# AT24-Timer.net
KiCad netlist of a schematic drawn in EAGLE
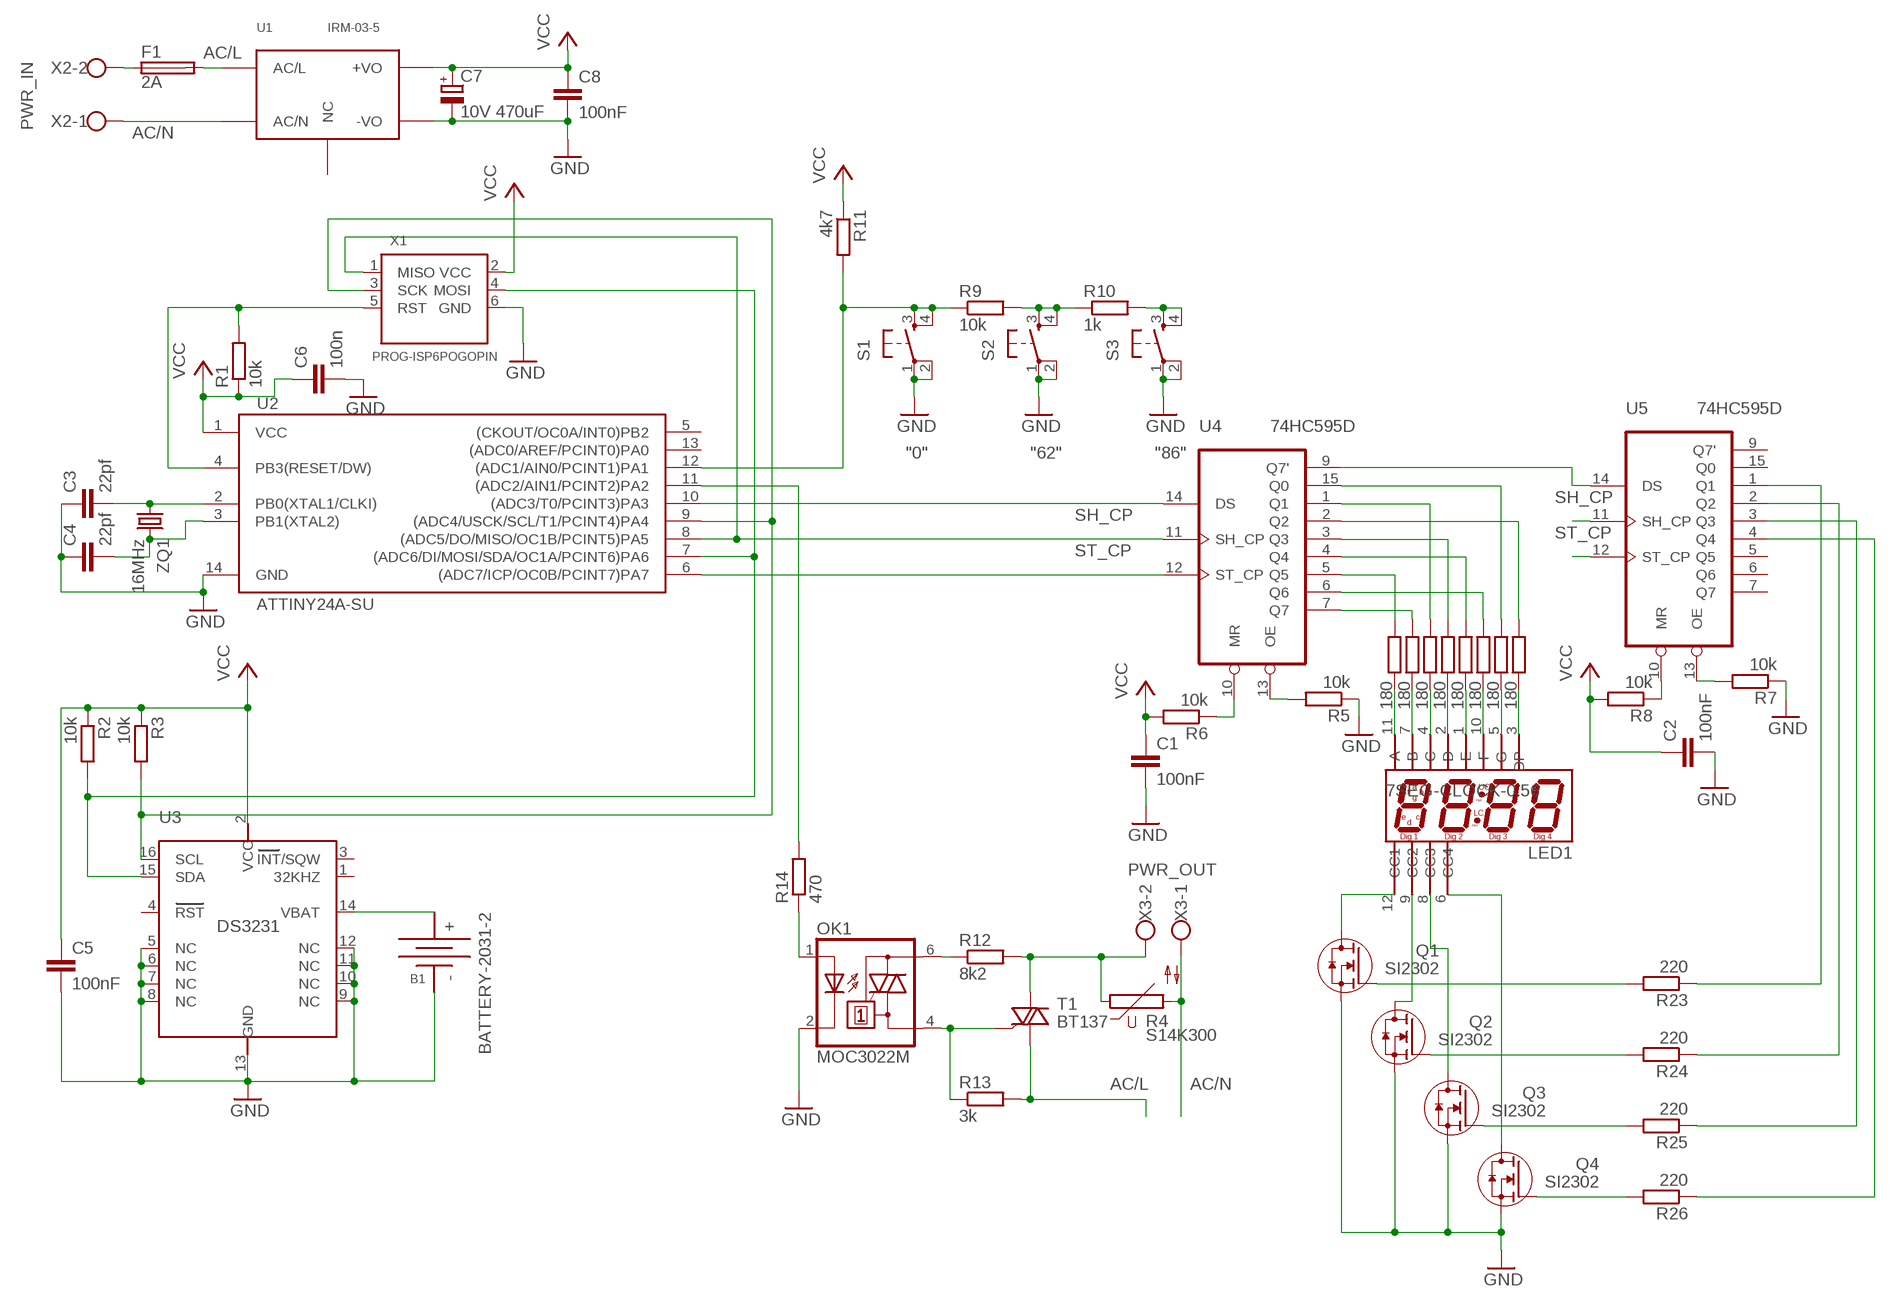
[diagram p0: schematic, sheet 1]

(export (version "E")
  (design (tool "Eeschema 10.0.6"))
  (components
    (comp (ref "B1")
      (value "BATTERY-2031-2")
      (footprint "eagle-import:BTH2032-2")
      (libsource (lib "eagle-import") (part "BATTERY-2031-2"))
    )
    (comp (ref "C1")
      (value "100nF")
      (footprint "eagle-import:C0603")
      (libsource (lib "eagle-import") (part "C-EUC0603"))
    )
    (comp (ref "C2")
      (value "100nF")
      (footprint "eagle-import:C0603")
      (libsource (lib "eagle-import") (part "C-EUC0603"))
    )
    (comp (ref "C3")
      (value "22pf")
      (footprint "eagle-import:C0603")
      (libsource (lib "eagle-import") (part "C-EUC0603"))
    )
    (comp (ref "C4")
      (value "22pf")
      (footprint "eagle-import:C0603")
      (libsource (lib "eagle-import") (part "C-EUC0603"))
    )
    (comp (ref "C5")
      (value "100nF")
      (footprint "eagle-import:C0603")
      (libsource (lib "eagle-import") (part "C-EUC0603"))
    )
    (comp (ref "C6")
      (value "100n")
      (footprint "eagle-import:C0603")
      (libsource (lib "eagle-import") (part "C-EUC0603"))
    )
    (comp (ref "C7")
      (value "10V 470uF")
      (footprint "eagle-import:D_7343-31W")
      (libsource (lib "eagle-import") (part "CPOL-EUD/7343-31W"))
    )
    (comp (ref "C8")
      (value "100nF")
      (footprint "eagle-import:C0805")
      (libsource (lib "eagle-import") (part "C-EUC0805"))
    )
    (comp (ref "F1")
      (value "2A")
      (footprint "eagle-import:SH22,5A")
      (fields (field (name "MPN") "0031.7701.11"))
      (libsource (lib "eagle-import") (part "SH22,5A"))
    )
    (comp (ref "LED1")
      (value "7SEG-CLOCK-0.56")
      (footprint "eagle-import:7SEG_4DIG_0.56")
      (libsource (lib "eagle-import") (part "7SEG-CLOCK-0.56"))
    )
    (comp (ref "OK1")
      (value "MOC3022M")
      (footprint "eagle-import:DIL06")
      (fields (field (name "MF") "FAIRCHILD SEMICONDUCTOR") (field (name "MPN") "MOC3022-M"))
      (libsource (lib "eagle-import") (part "MOC30M22"))
    )
    (comp (ref "Q1")
      (value "SI2302")
      (footprint "eagle-import:SOT-23-GSD")
      (libsource (lib "eagle-import") (part "SI2302"))
    )
    (comp (ref "Q2")
      (value "SI2302")
      (footprint "eagle-import:SOT-23-GSD")
      (libsource (lib "eagle-import") (part "SI2302"))
    )
    (comp (ref "Q3")
      (value "SI2302")
      (footprint "eagle-import:SOT-23-GSD")
      (libsource (lib "eagle-import") (part "SI2302"))
    )
    (comp (ref "Q4")
      (value "SI2302")
      (footprint "eagle-import:SOT-23-GSD")
      (libsource (lib "eagle-import") (part "SI2302"))
    )
    (comp (ref "R1")
      (value "10k")
      (footprint "eagle-import:R0805")
      (libsource (lib "eagle-import") (part "R-EU_R0805"))
    )
    (comp (ref "R2")
      (value "10k")
      (footprint "eagle-import:R0805")
      (libsource (lib "eagle-import") (part "R-EU_R0805"))
    )
    (comp (ref "R3")
      (value "10k")
      (footprint "eagle-import:R0805")
      (libsource (lib "eagle-import") (part "R-EU_R0805"))
    )
    (comp (ref "R4")
      (value "S14K300")
      (footprint "eagle-import:S14K300")
      (libsource (lib "eagle-import") (part "S14K300"))
    )
    (comp (ref "R5")
      (value "10k")
      (footprint "eagle-import:R0805")
      (libsource (lib "eagle-import") (part "R-EU_R0805"))
    )
    (comp (ref "R6")
      (value "10k")
      (footprint "eagle-import:R0805")
      (libsource (lib "eagle-import") (part "R-EU_R0805"))
    )
    (comp (ref "R7")
      (value "10k")
      (footprint "eagle-import:R0805")
      (libsource (lib "eagle-import") (part "R-EU_R0805"))
    )
    (comp (ref "R8")
      (value "10k")
      (footprint "eagle-import:R0805")
      (libsource (lib "eagle-import") (part "R-EU_R0805"))
    )
    (comp (ref "R9")
      (value "10k")
      (footprint "eagle-import:R0805")
      (libsource (lib "eagle-import") (part "R-EU_R0805"))
    )
    (comp (ref "R10")
      (value "1k")
      (footprint "eagle-import:R0805")
      (libsource (lib "eagle-import") (part "R-EU_R0805"))
    )
    (comp (ref "R11")
      (value "4k7")
      (footprint "eagle-import:R0805")
      (libsource (lib "eagle-import") (part "R-EU_R0805"))
    )
    (comp (ref "R12")
      (value "8k2")
      (footprint "eagle-import:0207_7")
      (libsource (lib "eagle-import") (part "R-EU_0207/7"))
    )
    (comp (ref "R13")
      (value "3k")
      (footprint "eagle-import:0207_7")
      (libsource (lib "eagle-import") (part "R-EU_0207/7"))
    )
    (comp (ref "R14")
      (value "470")
      (footprint "eagle-import:R0805")
      (libsource (lib "eagle-import") (part "R-EU_R0805"))
    )
    (comp (ref "R15")
      (value "180")
      (footprint "eagle-import:R0805")
      (libsource (lib "eagle-import") (part "R-EU_R0805"))
    )
    (comp (ref "R16")
      (value "180")
      (footprint "eagle-import:R0805")
      (libsource (lib "eagle-import") (part "R-EU_R0805"))
    )
    (comp (ref "R17")
      (value "180")
      (footprint "eagle-import:R0805")
      (libsource (lib "eagle-import") (part "R-EU_R0805"))
    )
    (comp (ref "R18")
      (value "180")
      (footprint "eagle-import:R0805")
      (libsource (lib "eagle-import") (part "R-EU_R0805"))
    )
    (comp (ref "R19")
      (value "180")
      (footprint "eagle-import:R0805")
      (libsource (lib "eagle-import") (part "R-EU_R0805"))
    )
    (comp (ref "R20")
      (value "180")
      (footprint "eagle-import:R0805")
      (libsource (lib "eagle-import") (part "R-EU_R0805"))
    )
    (comp (ref "R21")
      (value "180")
      (footprint "eagle-import:R0805")
      (libsource (lib "eagle-import") (part "R-EU_R0805"))
    )
    (comp (ref "R22")
      (value "180")
      (footprint "eagle-import:R0805")
      (libsource (lib "eagle-import") (part "R-EU_R0805"))
    )
    (comp (ref "R23")
      (value "220")
      (footprint "eagle-import:R0805")
      (libsource (lib "eagle-import") (part "R-EU_R0805"))
    )
    (comp (ref "R24")
      (value "220")
      (footprint "eagle-import:R0805")
      (libsource (lib "eagle-import") (part "R-EU_R0805"))
    )
    (comp (ref "R25")
      (value "220")
      (footprint "eagle-import:R0805")
      (libsource (lib "eagle-import") (part "R-EU_R0805"))
    )
    (comp (ref "R26")
      (value "220")
      (footprint "eagle-import:R0805")
      (libsource (lib "eagle-import") (part "R-EU_R0805"))
    )
    (comp (ref "S1")
      (value "DTS-6")
      (footprint "eagle-import:DTS-6")
      (libsource (lib "eagle-import") (part "DTS-6"))
    )
    (comp (ref "S2")
      (value "DTS-6")
      (footprint "eagle-import:DTS-6")
      (libsource (lib "eagle-import") (part "DTS-6"))
    )
    (comp (ref "S3")
      (value "DTS-6")
      (footprint "eagle-import:DTS-6")
      (libsource (lib "eagle-import") (part "DTS-6"))
    )
    (comp (ref "T1")
      (value "BT137")
      (footprint "eagle-import:TO220AB")
      (libsource (lib "eagle-import") (part "BT136"))
    )
    (comp (ref "U1")
      (value "IRM-03-5")
      (footprint "eagle-import:IRM-03-_")
      (libsource (lib "eagle-import") (part "IRM-03-5"))
    )
    (comp (ref "U2")
      (value "ATTINY24A-SU")
      (footprint "eagle-import:SO14")
      (libsource (lib "eagle-import") (part "ATTINY24A-SU"))
    )
    (comp (ref "U3")
      (value "DS3231")
      (footprint "eagle-import:SO16L")
      (libsource (lib "eagle-import") (part "DS3231"))
    )
    (comp (ref "U4")
      (value "74HC595D")
      (footprint "eagle-import:SO16")
      (libsource (lib "eagle-import") (part "74595DHC"))
    )
    (comp (ref "U5")
      (value "74HC595D")
      (footprint "eagle-import:SO16")
      (libsource (lib "eagle-import") (part "74595DHC"))
    )
    (comp (ref "X1")
      (value "PROG-ISP6POGOPIN")
      (footprint "eagle-import:PROG_POGOPIN")
      (libsource (lib "eagle-import") (part "PROG-ISP6POGOPIN"))
    )
    (comp (ref "X2")
      (value "PWR_IN")
      (footprint "eagle-import:W237-102")
      (fields (field (name "MPN") "237-102"))
      (libsource (lib "eagle-import") (part "W237-102"))
    )
    (comp (ref "X3")
      (value "PWR_OUT")
      (footprint "eagle-import:W237-102")
      (fields (field (name "MPN") "237-102"))
      (libsource (lib "eagle-import") (part "W237-102"))
    )
    (comp (ref "ZQ1")
      (value "16MHz")
      (footprint "eagle-import:HC49_S")
      (libsource (lib "eagle-import") (part "CRYSTALHC49S"))
    )
  )
  (nets
    (net (code "1") (name "/AC{slash}L") (class "Default")
      (node (ref "F1") (pin "2") (pinfunction "2_2") (pintype "passive"))
      (node (ref "R13") (pin "2") (pinfunction "2_2") (pintype "passive"))
      (node (ref "T1") (pin "1") (pinfunction "A1_1") (pintype "passive"))
      (node (ref "U1") (pin "P$1") (pinfunction "AC/L_P$1") (pintype "power_in"))
    )
    (net (code "2") (name "/AC{slash}N") (class "Default")
      (node (ref "R4") (pin "2") (pinfunction "2_2") (pintype "passive"))
      (node (ref "U1") (pin "P$2") (pinfunction "AC/N_P$2") (pintype "power_in"))
      (node (ref "X2") (pin "1") (pinfunction "KL_1") (pintype "passive"))
      (node (ref "X3") (pin "1") (pinfunction "KL_1") (pintype "passive"))
    )
    (net (code "3") (name "/NC") (class "Default")
      (node (ref "U1") (pin "P$3") (pinfunction "NC_P$3") (pintype "power_in"))
    )
    (net (code "4") (name "/SH_CP") (class "Default")
      (node (ref "U2") (pin "8") (pinfunction "(ADC5/DO/MISO/OC1B/PCINT5)PA5_8") (pintype "bidirectional"))
      (node (ref "U4") (pin "11") (pinfunction "SH_CP_11") (pintype "input"))
      (node (ref "U5") (pin "11") (pinfunction "SH_CP_11") (pintype "input"))
      (node (ref "X1") (pin "1") (pinfunction "MISO_1") (pintype "bidirectional"))
    )
    (net (code "5") (name "/ST_CP") (class "Default")
      (node (ref "U2") (pin "6") (pinfunction "(ADC7/ICP/OC0B/PCINT7)PA7_6") (pintype "bidirectional"))
      (node (ref "U4") (pin "12") (pinfunction "ST_CP_12") (pintype "input"))
      (node (ref "U5") (pin "12") (pinfunction "ST_CP_12") (pintype "input"))
    )
    (net (code "6") (name "GND") (class "Default")
      (node (ref "B1") (pin "-") (pinfunction "-_-") (pintype "power_in"))
      (node (ref "C1") (pin "2") (pinfunction "2_2") (pintype "passive"))
      (node (ref "C2") (pin "2") (pinfunction "2_2") (pintype "passive"))
      (node (ref "C3") (pin "1") (pinfunction "1_1") (pintype "passive"))
      (node (ref "C4") (pin "1") (pinfunction "1_1") (pintype "passive"))
      (node (ref "C5") (pin "2") (pinfunction "2_2") (pintype "passive"))
      (node (ref "C6") (pin "2") (pinfunction "2_2") (pintype "passive"))
      (node (ref "C7") (pin "-") (pinfunction "-_-") (pintype "passive"))
      (node (ref "C8") (pin "2") (pinfunction "2_2") (pintype "passive"))
      (node (ref "OK1") (pin "2") (pinfunction "C_2") (pintype "passive"))
      (node (ref "Q1") (pin "S") (pinfunction "S_S") (pintype "passive"))
      (node (ref "Q2") (pin "S") (pinfunction "S_S") (pintype "passive"))
      (node (ref "Q3") (pin "S") (pinfunction "S_S") (pintype "passive"))
      (node (ref "Q4") (pin "S") (pinfunction "S_S") (pintype "passive"))
      (node (ref "R5") (pin "1") (pinfunction "1_1") (pintype "passive"))
      (node (ref "R7") (pin "1") (pinfunction "1_1") (pintype "passive"))
      (node (ref "S1") (pin "1") (pinfunction "1_1") (pintype "passive"))
      (node (ref "S1") (pin "2") (pinfunction "2_2") (pintype "passive"))
      (node (ref "S2") (pin "1") (pinfunction "1_1") (pintype "passive"))
      (node (ref "S2") (pin "2") (pinfunction "2_2") (pintype "passive"))
      (node (ref "S3") (pin "1") (pinfunction "1_1") (pintype "passive"))
      (node (ref "S3") (pin "2") (pinfunction "2_2") (pintype "passive"))
      (node (ref "U1") (pin "P$4") (pinfunction "-VO_P$4") (pintype "power_in"))
      (node (ref "U2") (pin "14") (pinfunction "GND_14") (pintype "power_in"))
      (node (ref "U3") (pin "10") (pinfunction "NC_10") (pintype "bidirectional"))
      (node (ref "U3") (pin "11") (pinfunction "NC_11") (pintype "bidirectional"))
      (node (ref "U3") (pin "12") (pinfunction "NC_12") (pintype "bidirectional"))
      (node (ref "U3") (pin "13") (pinfunction "GND_13") (pintype "power_in"))
      (node (ref "U3") (pin "5") (pinfunction "NC_5") (pintype "bidirectional"))
      (node (ref "U3") (pin "6") (pinfunction "NC_6") (pintype "bidirectional"))
      (node (ref "U3") (pin "7") (pinfunction "NC_7") (pintype "bidirectional"))
      (node (ref "U3") (pin "8") (pinfunction "NC_8") (pintype "bidirectional"))
      (node (ref "U3") (pin "9") (pinfunction "NC_9") (pintype "bidirectional"))
      (node (ref "X1") (pin "6") (pinfunction "GND_6") (pintype "power_in"))
    )
    (net (code "7") (name "Net-(LED1-A)") (class "Default")
      (node (ref "LED1") (pin "11") (pinfunction "A_11") (pintype "input"))
      (node (ref "R15") (pin "2") (pinfunction "2_2") (pintype "passive"))
    )
    (net (code "8") (name "Net-(LED1-B)") (class "Default")
      (node (ref "LED1") (pin "7") (pinfunction "B_7") (pintype "input"))
      (node (ref "R16") (pin "2") (pinfunction "2_2") (pintype "passive"))
    )
    (net (code "9") (name "Net-(LED1-C)") (class "Default")
      (node (ref "LED1") (pin "4") (pinfunction "C_4") (pintype "input"))
      (node (ref "R17") (pin "2") (pinfunction "2_2") (pintype "passive"))
    )
    (net (code "10") (name "Net-(LED1-CC1)") (class "Default")
      (node (ref "LED1") (pin "12") (pinfunction "CC1_12") (pintype "input"))
      (node (ref "Q1") (pin "D") (pinfunction "D_D") (pintype "passive"))
    )
    (net (code "11") (name "Net-(LED1-CC2)") (class "Default")
      (node (ref "LED1") (pin "9") (pinfunction "CC2_9") (pintype "input"))
      (node (ref "Q2") (pin "D") (pinfunction "D_D") (pintype "passive"))
    )
    (net (code "12") (name "Net-(LED1-CC3)") (class "Default")
      (node (ref "LED1") (pin "8") (pinfunction "CC3_8") (pintype "input"))
      (node (ref "Q3") (pin "D") (pinfunction "D_D") (pintype "passive"))
    )
    (net (code "13") (name "Net-(LED1-CC4)") (class "Default")
      (node (ref "LED1") (pin "6") (pinfunction "CC4_6") (pintype "input"))
      (node (ref "Q4") (pin "D") (pinfunction "D_D") (pintype "passive"))
    )
    (net (code "14") (name "Net-(LED1-D)") (class "Default")
      (node (ref "LED1") (pin "2") (pinfunction "D_2") (pintype "input"))
      (node (ref "R18") (pin "2") (pinfunction "2_2") (pintype "passive"))
    )
    (net (code "15") (name "Net-(LED1-DP)") (class "Default")
      (node (ref "LED1") (pin "3") (pinfunction "DP_3") (pintype "input"))
      (node (ref "R22") (pin "2") (pinfunction "2_2") (pintype "passive"))
    )
    (net (code "16") (name "Net-(LED1-E)") (class "Default")
      (node (ref "LED1") (pin "1") (pinfunction "E_1") (pintype "input"))
      (node (ref "R19") (pin "2") (pinfunction "2_2") (pintype "passive"))
    )
    (net (code "17") (name "Net-(LED1-F)") (class "Default")
      (node (ref "LED1") (pin "10") (pinfunction "F_10") (pintype "input"))
      (node (ref "R20") (pin "2") (pinfunction "2_2") (pintype "passive"))
    )
    (net (code "18") (name "Net-(LED1-G)") (class "Default")
      (node (ref "LED1") (pin "5") (pinfunction "G_5") (pintype "input"))
      (node (ref "R21") (pin "2") (pinfunction "2_2") (pintype "passive"))
    )
    (net (code "19") (name "Net-(OK1-A)") (class "Default")
      (node (ref "OK1") (pin "1") (pinfunction "A_1") (pintype "passive"))
      (node (ref "R14") (pin "1") (pinfunction "1_1") (pintype "passive"))
    )
    (net (code "20") (name "Net-(OK1-A1)") (class "Default")
      (node (ref "OK1") (pin "4") (pinfunction "A1_4") (pintype "passive"))
      (node (ref "R13") (pin "1") (pinfunction "1_1") (pintype "passive"))
      (node (ref "T1") (pin "3") (pinfunction "G_3") (pintype "passive"))
    )
    (net (code "21") (name "Net-(OK1-A2)") (class "Default")
      (node (ref "OK1") (pin "6") (pinfunction "A2_6") (pintype "passive"))
      (node (ref "R12") (pin "1") (pinfunction "1_1") (pintype "passive"))
    )
    (net (code "22") (name "Net-(Q1-PadG)") (class "Default")
      (node (ref "Q1") (pin "G") (pinfunction "G_G") (pintype "passive"))
      (node (ref "R23") (pin "2") (pinfunction "2_2") (pintype "passive"))
    )
    (net (code "23") (name "Net-(Q2-PadG)") (class "Default")
      (node (ref "Q2") (pin "G") (pinfunction "G_G") (pintype "passive"))
      (node (ref "R24") (pin "2") (pinfunction "2_2") (pintype "passive"))
    )
    (net (code "24") (name "Net-(Q3-PadG)") (class "Default")
      (node (ref "Q3") (pin "G") (pinfunction "G_G") (pintype "passive"))
      (node (ref "R25") (pin "2") (pinfunction "2_2") (pintype "passive"))
    )
    (net (code "25") (name "Net-(Q4-PadG)") (class "Default")
      (node (ref "Q4") (pin "G") (pinfunction "G_G") (pintype "passive"))
      (node (ref "R26") (pin "2") (pinfunction "2_2") (pintype "passive"))
    )
    (net (code "26") (name "Net-(R10-Pad1)") (class "Default")
      (node (ref "R10") (pin "1") (pinfunction "1_1") (pintype "passive"))
      (node (ref "R9") (pin "2") (pinfunction "2_2") (pintype "passive"))
      (node (ref "S2") (pin "3") (pinfunction "3_3") (pintype "passive"))
      (node (ref "S2") (pin "4") (pinfunction "4_4") (pintype "passive"))
    )
    (net (code "27") (name "Net-(R10-Pad2)") (class "Default")
      (node (ref "R10") (pin "2") (pinfunction "2_2") (pintype "passive"))
      (node (ref "S3") (pin "3") (pinfunction "3_3") (pintype "passive"))
      (node (ref "S3") (pin "4") (pinfunction "4_4") (pintype "passive"))
    )
    (net (code "28") (name "Net-(T1-A2)") (class "Default")
      (node (ref "R12") (pin "2") (pinfunction "2_2") (pintype "passive"))
      (node (ref "R4") (pin "1") (pinfunction "1_1") (pintype "passive"))
      (node (ref "T1") (pin "2") (pinfunction "A2_2") (pintype "passive"))
      (node (ref "X3") (pin "2") (pinfunction "KL_2") (pintype "passive"))
    )
    (net (code "29") (name "Net-(U2-(ADC1{slash}AIN0{slash}PCINT1)PA1)") (class "Default")
      (node (ref "R11") (pin "2") (pinfunction "2_2") (pintype "passive"))
      (node (ref "R9") (pin "1") (pinfunction "1_1") (pintype "passive"))
      (node (ref "S1") (pin "3") (pinfunction "3_3") (pintype "passive"))
      (node (ref "S1") (pin "4") (pinfunction "4_4") (pintype "passive"))
      (node (ref "U2") (pin "12") (pinfunction "(ADC1/AIN0/PCINT1)PA1_12") (pintype "bidirectional"))
    )
    (net (code "30") (name "Net-(U2-(ADC2{slash}AIN1{slash}PCINT2)PA2)") (class "Default")
      (node (ref "R14") (pin "2") (pinfunction "2_2") (pintype "passive"))
      (node (ref "U2") (pin "11") (pinfunction "(ADC2/AIN1/PCINT2)PA2_11") (pintype "bidirectional"))
    )
    (net (code "31") (name "Net-(U2-(ADC3{slash}T0{slash}PCINT3)PA3)") (class "Default")
      (node (ref "U2") (pin "10") (pinfunction "(ADC3/T0/PCINT3)PA3_10") (pintype "bidirectional"))
      (node (ref "U4") (pin "14") (pinfunction "DS_14") (pintype "input"))
    )
    (net (code "32") (name "Net-(U2-(ADC4{slash}USCK{slash}SCL{slash}T1{slash}PCINT4)PA4)") (class "Default")
      (node (ref "R3") (pin "2") (pinfunction "2_2") (pintype "passive"))
      (node (ref "U2") (pin "9") (pinfunction "(ADC4/USCK/SCL/T1/PCINT4)PA4_9") (pintype "bidirectional"))
      (node (ref "U3") (pin "16") (pinfunction "SCL_16") (pintype "bidirectional"))
      (node (ref "X1") (pin "3") (pinfunction "SCK_3") (pintype "bidirectional"))
    )
    (net (code "33") (name "Net-(U2-(ADC6{slash}DI{slash}MOSI{slash}SDA{slash}OC1A{slash}PCINT6)PA6)") (class "Default")
      (node (ref "R2") (pin "2") (pinfunction "2_2") (pintype "passive"))
      (node (ref "U2") (pin "7") (pinfunction "(ADC6/DI/MOSI/SDA/OC1A/PCINT6)PA6_7") (pintype "bidirectional"))
      (node (ref "U3") (pin "15") (pinfunction "SDA_15") (pintype "bidirectional"))
      (node (ref "X1") (pin "4") (pinfunction "MOSI_4") (pintype "bidirectional"))
    )
    (net (code "34") (name "Net-(U2-PB0(XTAL1{slash}CLKI))") (class "Default")
      (node (ref "C3") (pin "2") (pinfunction "2_2") (pintype "passive"))
      (node (ref "U2") (pin "2") (pinfunction "PB0(XTAL1/CLKI)_2") (pintype "bidirectional"))
      (node (ref "ZQ1") (pin "1") (pinfunction "1_1") (pintype "passive"))
    )
    (net (code "35") (name "Net-(U2-PB1(XTAL2))") (class "Default")
      (node (ref "C4") (pin "2") (pinfunction "2_2") (pintype "passive"))
      (node (ref "U2") (pin "3") (pinfunction "PB1(XTAL2)_3") (pintype "bidirectional"))
      (node (ref "ZQ1") (pin "2") (pinfunction "2_2") (pintype "passive"))
    )
    (net (code "36") (name "Net-(U2-PB3(RESET{slash}DW))") (class "Default")
      (node (ref "R1") (pin "2") (pinfunction "2_2") (pintype "passive"))
      (node (ref "U2") (pin "4") (pinfunction "PB3(RESET/DW)_4") (pintype "bidirectional"))
      (node (ref "X1") (pin "5") (pinfunction "RST_5") (pintype "bidirectional"))
    )
    (net (code "37") (name "Net-(U3-VBAT)") (class "Default")
      (node (ref "B1") (pin "+") (pinfunction "+_+") (pintype "power_in"))
      (node (ref "U3") (pin "14") (pinfunction "VBAT_14") (pintype "bidirectional"))
    )
    (net (code "38") (name "Net-(U4A-MR)") (class "Default")
      (node (ref "R6") (pin "1") (pinfunction "1_1") (pintype "passive"))
      (node (ref "U4") (pin "10") (pinfunction "MR_10") (pintype "input"))
    )
    (net (code "39") (name "Net-(U4A-OE)") (class "Default")
      (node (ref "R5") (pin "2") (pinfunction "2_2") (pintype "passive"))
      (node (ref "U4") (pin "13") (pinfunction "OE_13") (pintype "input"))
    )
    (net (code "40") (name "Net-(U4A-Q0)") (class "Default")
      (node (ref "R21") (pin "1") (pinfunction "1_1") (pintype "passive"))
      (node (ref "U4") (pin "15") (pinfunction "Q0_15") (pintype "output"))
    )
    (net (code "41") (name "Net-(U4A-Q1)") (class "Default")
      (node (ref "R17") (pin "1") (pinfunction "1_1") (pintype "passive"))
      (node (ref "U4") (pin "1") (pinfunction "Q1_1") (pintype "output"))
    )
    (net (code "42") (name "Net-(U4A-Q2)") (class "Default")
      (node (ref "R22") (pin "1") (pinfunction "1_1") (pintype "passive"))
      (node (ref "U4") (pin "2") (pinfunction "Q2_2") (pintype "output"))
    )
    (net (code "43") (name "Net-(U4A-Q3)") (class "Default")
      (node (ref "R18") (pin "1") (pinfunction "1_1") (pintype "passive"))
      (node (ref "U4") (pin "3") (pinfunction "Q3_3") (pintype "output"))
    )
    (net (code "44") (name "Net-(U4A-Q4)") (class "Default")
      (node (ref "R19") (pin "1") (pinfunction "1_1") (pintype "passive"))
      (node (ref "U4") (pin "4") (pinfunction "Q4_4") (pintype "output"))
    )
    (net (code "45") (name "Net-(U4A-Q5)") (class "Default")
      (node (ref "R15") (pin "1") (pinfunction "1_1") (pintype "passive"))
      (node (ref "U4") (pin "5") (pinfunction "Q5_5") (pintype "output"))
    )
    (net (code "46") (name "Net-(U4A-Q6)") (class "Default")
      (node (ref "R20") (pin "1") (pinfunction "1_1") (pintype "passive"))
      (node (ref "U4") (pin "6") (pinfunction "Q6_6") (pintype "output"))
    )
    (net (code "47") (name "Net-(U4A-Q7')") (class "Default")
      (node (ref "U4") (pin "9") (pinfunction "Q7'_9") (pintype "output"))
      (node (ref "U5") (pin "14") (pinfunction "DS_14") (pintype "input"))
    )
    (net (code "48") (name "Net-(U4A-Q7)") (class "Default")
      (node (ref "R16") (pin "1") (pinfunction "1_1") (pintype "passive"))
      (node (ref "U4") (pin "7") (pinfunction "Q7_7") (pintype "output"))
    )
    (net (code "49") (name "Net-(U5A-MR)") (class "Default")
      (node (ref "R8") (pin "1") (pinfunction "1_1") (pintype "passive"))
      (node (ref "U5") (pin "10") (pinfunction "MR_10") (pintype "input"))
    )
    (net (code "50") (name "Net-(U5A-OE)") (class "Default")
      (node (ref "R7") (pin "2") (pinfunction "2_2") (pintype "passive"))
      (node (ref "U5") (pin "13") (pinfunction "OE_13") (pintype "input"))
    )
    (net (code "51") (name "Net-(U5A-Q1)") (class "Default")
      (node (ref "R23") (pin "1") (pinfunction "1_1") (pintype "passive"))
      (node (ref "U5") (pin "1") (pinfunction "Q1_1") (pintype "output"))
    )
    (net (code "52") (name "Net-(U5A-Q2)") (class "Default")
      (node (ref "R24") (pin "1") (pinfunction "1_1") (pintype "passive"))
      (node (ref "U5") (pin "2") (pinfunction "Q2_2") (pintype "output"))
    )
    (net (code "53") (name "Net-(U5A-Q3)") (class "Default")
      (node (ref "R25") (pin "1") (pinfunction "1_1") (pintype "passive"))
      (node (ref "U5") (pin "3") (pinfunction "Q3_3") (pintype "output"))
    )
    (net (code "54") (name "Net-(U5A-Q4)") (class "Default")
      (node (ref "R26") (pin "1") (pinfunction "1_1") (pintype "passive"))
      (node (ref "U5") (pin "4") (pinfunction "Q4_4") (pintype "output"))
    )
    (net (code "55") (name "Net-(X2B-KL)") (class "Default")
      (node (ref "F1") (pin "1") (pinfunction "1_1") (pintype "passive"))
      (node (ref "X2") (pin "2") (pinfunction "KL_2") (pintype "passive"))
    )
    (net (code "56") (name "VCC") (class "Default")
      (node (ref "C1") (pin "1") (pinfunction "1_1") (pintype "passive"))
      (node (ref "C2") (pin "1") (pinfunction "1_1") (pintype "passive"))
      (node (ref "C5") (pin "1") (pinfunction "1_1") (pintype "passive"))
      (node (ref "C6") (pin "1") (pinfunction "1_1") (pintype "passive"))
      (node (ref "C7") (pin "+") (pinfunction "+_+") (pintype "passive"))
      (node (ref "C8") (pin "1") (pinfunction "1_1") (pintype "passive"))
      (node (ref "R1") (pin "1") (pinfunction "1_1") (pintype "passive"))
      (node (ref "R11") (pin "1") (pinfunction "1_1") (pintype "passive"))
      (node (ref "R2") (pin "1") (pinfunction "1_1") (pintype "passive"))
      (node (ref "R3") (pin "1") (pinfunction "1_1") (pintype "passive"))
      (node (ref "R6") (pin "2") (pinfunction "2_2") (pintype "passive"))
      (node (ref "R8") (pin "2") (pinfunction "2_2") (pintype "passive"))
      (node (ref "U1") (pin "P$5") (pinfunction "+VO_P$5") (pintype "power_in"))
      (node (ref "U2") (pin "1") (pinfunction "VCC_1") (pintype "power_in"))
      (node (ref "U3") (pin "2") (pinfunction "VCC_2") (pintype "power_in"))
      (node (ref "X1") (pin "2") (pinfunction "VCC_2") (pintype "bidirectional"))
    )
    (net (code "57") (name "unconnected-(U2-(ADC0{slash}AREF{slash}PCINT0)PA0-Pad13)") (class "Default")
      (node (ref "U2") (pin "13") (pinfunction "(ADC0/AREF/PCINT0)PA0_13") (pintype "bidirectional"))
    )
    (net (code "58") (name "unconnected-(U2-(CKOUT{slash}OC0A{slash}INT0)PB2-Pad5)") (class "Default")
      (node (ref "U2") (pin "5") (pinfunction "(CKOUT/OC0A/INT0)PB2_5") (pintype "bidirectional"))
    )
    (net (code "59") (name "unconnected-(U3-32KHZ-Pad1)") (class "Default")
      (node (ref "U3") (pin "1") (pinfunction "32KHZ_1") (pintype "bidirectional"))
    )
    (net (code "60") (name "unconnected-(U3-INT{slash}SQW-Pad3)") (class "Default")
      (node (ref "U3") (pin "3") (pinfunction "INT/SQW_3") (pintype "bidirectional"))
    )
    (net (code "61") (name "unconnected-(U3-RST-Pad4)") (class "Default")
      (node (ref "U3") (pin "4") (pinfunction "RST_4") (pintype "bidirectional"))
    )
    (net (code "62") (name "unconnected-(U5A-Q0-Pad15)") (class "Default")
      (node (ref "U5") (pin "15") (pinfunction "Q0_15") (pintype "output"))
    )
    (net (code "63") (name "unconnected-(U5A-Q5-Pad5)") (class "Default")
      (node (ref "U5") (pin "5") (pinfunction "Q5_5") (pintype "output"))
    )
    (net (code "64") (name "unconnected-(U5A-Q6-Pad6)") (class "Default")
      (node (ref "U5") (pin "6") (pinfunction "Q6_6") (pintype "output"))
    )
    (net (code "65") (name "unconnected-(U5A-Q7'-Pad9)") (class "Default")
      (node (ref "U5") (pin "9") (pinfunction "Q7'_9") (pintype "output"))
    )
    (net (code "66") (name "unconnected-(U5A-Q7-Pad7)") (class "Default")
      (node (ref "U5") (pin "7") (pinfunction "Q7_7") (pintype "output"))
    )
  )
)
